# PWR_MT2492.net
KiCad netlist of a schematic drawn in Altium Designer
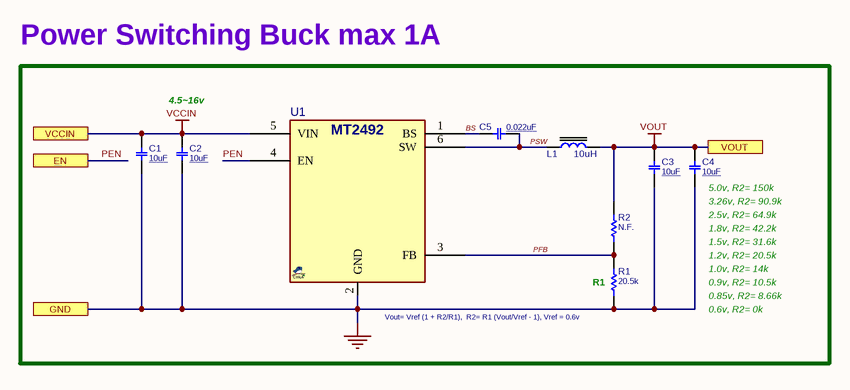
[diagram p0: PWR_MT2492.SchDoc]

(export (version "E")
  (design (tool "Eeschema 10.0.6"))
  (components
    (comp (ref "C1")
      (value "10uF")
      (footprint "C0603")
      (description "CAP, MLCC")
      (libsource (lib "passive_smd") (part "CAP_SMD_MLCC"))
    )
    (comp (ref "C2")
      (value "10uF")
      (footprint "C0603")
      (description "CAP, MLCC")
      (libsource (lib "passive_smd") (part "CAP_SMD_MLCC"))
    )
    (comp (ref "C3")
      (value "10uF")
      (footprint "C0603")
      (description "CAP, MLCC")
      (libsource (lib "passive_smd") (part "CAP_SMD_MLCC"))
    )
    (comp (ref "C4")
      (value "10uF")
      (footprint "C0603")
      (description "CAP, MLCC")
      (libsource (lib "passive_smd") (part "CAP_SMD_MLCC"))
    )
    (comp (ref "C5")
      (value "0.022uF")
      (footprint "C0603")
      (description "CAP, MLCC")
      (libsource (lib "passive_smd") (part "CAP_SMD_MLCC"))
    )
    (comp (ref "L1")
      (value "10uH")
      (footprint "L1210")
      (description "INDUCTOR, POWER, SMD")
      (fields (field (name "MANF") "Murata") (field (name "MANF_P#") "DFE322512F-100M"))
      (libsource (lib "passive_smd") (part "INDPWR_SMD"))
    )
    (comp (ref "R1")
      (value "20.5k")
      (footprint "R0603")
      (description "RESISTOR, SMD")
      (libsource (lib "passive_smd") (part "RES_SMD"))
    )
    (comp (ref "R2")
      (value "N.F.")
      (footprint "R0603")
      (description "RESISTOR, SMD")
      (libsource (lib "passive_smd") (part "RES_SMD"))
    )
    (comp (ref "U1")
      (value "MT2492")
      (footprint "SOT23_6")
      (description "REG, Switching, Buck, 2A, ADJ, 0.6MHz, 4.5~16VIN, SOT23-5")
      (fields (field (name "MANF") "Aerosemi"))
      (libsource (lib "pwr_switching_buck") (part "VREG_MT2492_SOT23"))
    )
  )
  (nets
    (net (code "1") (name "/BS") (class "Default")
      (node (ref "C5") (pin "1") (pinfunction "1_1") (pintype "passive"))
      (node (ref "U1") (pin "1") (pinfunction "BS_1") (pintype "power_in"))
    )
    (net (code "2") (name "/PEN") (class "Default")
      (node (ref "U1") (pin "4") (pinfunction "EN_4") (pintype "power_in"))
    )
    (net (code "3") (name "/PFB") (class "Default")
      (node (ref "R1") (pin "2") (pinfunction "2_2") (pintype "passive"))
      (node (ref "R2") (pin "1") (pinfunction "1_1") (pintype "passive"))
      (node (ref "U1") (pin "3") (pinfunction "FB_3") (pintype "power_in"))
    )
    (net (code "4") (name "/PSW") (class "Default")
      (node (ref "C5") (pin "2") (pinfunction "2_2") (pintype "passive"))
      (node (ref "L1") (pin "1") (pinfunction "1_1") (pintype "passive"))
      (node (ref "U1") (pin "6") (pinfunction "SW_6") (pintype "power_in"))
    )
    (net (code "5") (name "GND") (class "Default")
      (node (ref "C1") (pin "2") (pinfunction "2_2") (pintype "passive"))
      (node (ref "C2") (pin "2") (pinfunction "2_2") (pintype "passive"))
      (node (ref "C3") (pin "2") (pinfunction "2_2") (pintype "passive"))
      (node (ref "C4") (pin "2") (pinfunction "2_2") (pintype "passive"))
      (node (ref "R1") (pin "1") (pinfunction "1_1") (pintype "passive"))
      (node (ref "U1") (pin "2") (pinfunction "GND_2") (pintype "power_in"))
    )
    (net (code "6") (name "VCCIN") (class "Default")
      (node (ref "C1") (pin "1") (pinfunction "1_1") (pintype "passive"))
      (node (ref "C2") (pin "1") (pinfunction "1_1") (pintype "passive"))
      (node (ref "U1") (pin "5") (pinfunction "VIN_5") (pintype "power_in"))
    )
    (net (code "7") (name "VOUT") (class "Default")
      (node (ref "C3") (pin "1") (pinfunction "1_1") (pintype "passive"))
      (node (ref "C4") (pin "1") (pinfunction "1_1") (pintype "passive"))
      (node (ref "L1") (pin "2") (pinfunction "2_2") (pintype "passive"))
      (node (ref "R2") (pin "2") (pinfunction "2_2") (pintype "passive"))
    )
  )
)
